# PoEpi_proto.net
KiCad netlist of a schematic drawn in EAGLE
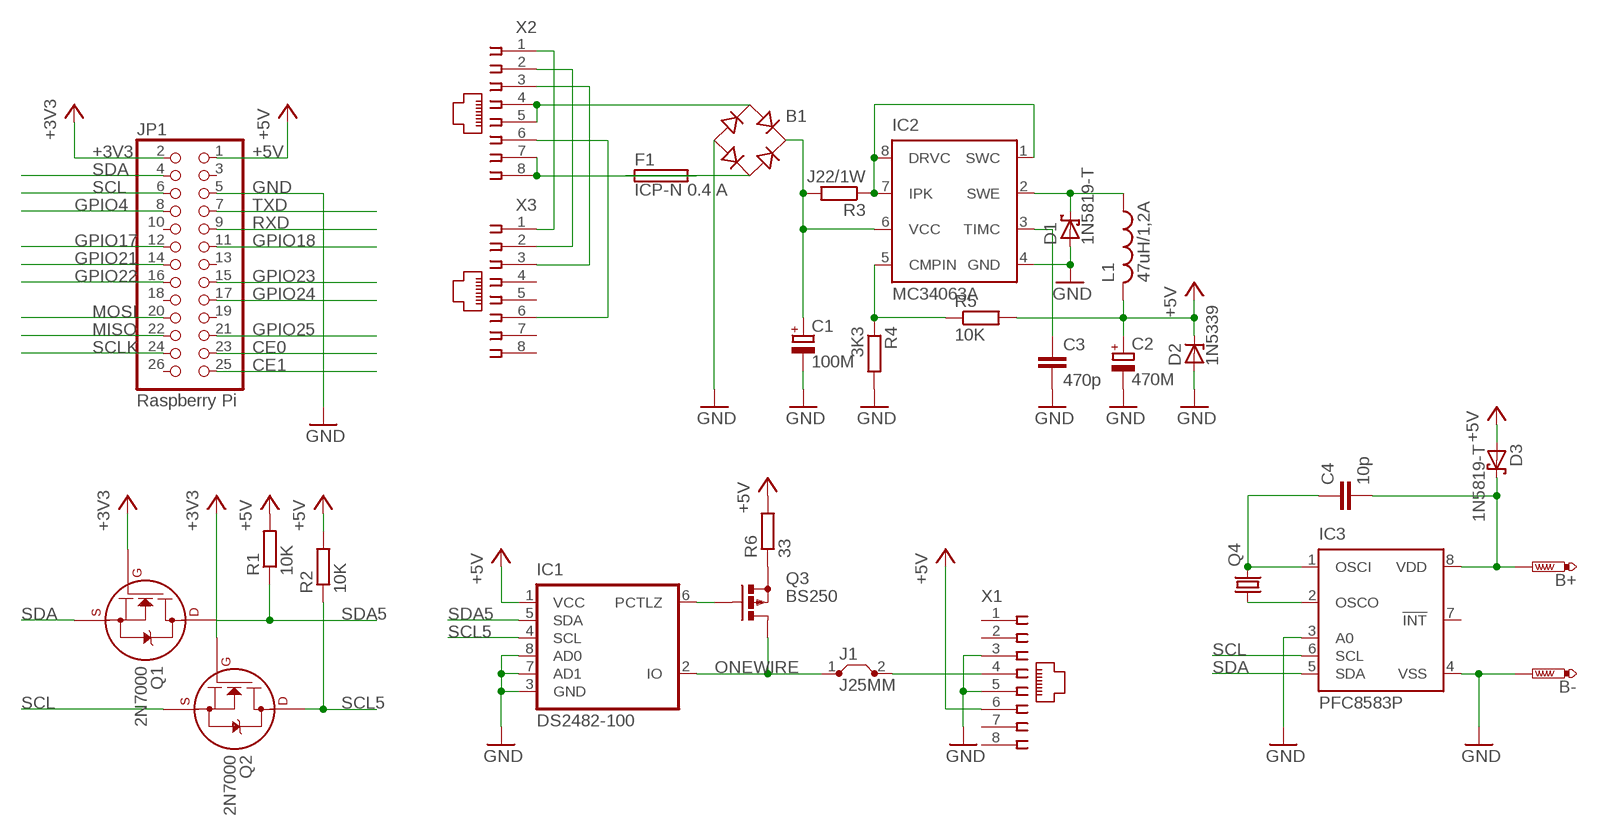
[diagram p0: schematic, sheet 1]

(export (version "E")
  (design (tool "Eeschema 10.0.6"))
  (components
    (comp (ref "B+")
      (value "PTR1PAD1-13Y")
      (footprint "eagle-import:P1-13Y")
      (libsource (lib "eagle-import") (part "PTR1PAD1-13Y"))
    )
    (comp (ref "B-")
      (value "PTR1PAD1-13Y")
      (footprint "eagle-import:P1-13Y")
      (libsource (lib "eagle-import") (part "PTR1PAD1-13Y"))
    )
    (comp (ref "B1")
      (value "B-DIL")
      (footprint "eagle-import:B-DIL")
      (libsource (lib "eagle-import") (part "B-DIL"))
    )
    (comp (ref "C1")
      (value "100M")
      (footprint "eagle-import:E3,5-8")
      (libsource (lib "eagle-import") (part "CPOL-EUE3.5-8"))
    )
    (comp (ref "C2")
      (value "470M")
      (footprint "eagle-import:E3,5-8")
      (libsource (lib "eagle-import") (part "CPOL-EUE3.5-8"))
    )
    (comp (ref "C3")
      (value "470p")
      (footprint "eagle-import:C050-024X044")
      (libsource (lib "eagle-import") (part "C-EU050-024X044"))
    )
    (comp (ref "C4")
      (value "10p")
      (footprint "eagle-import:C050-024X044")
      (libsource (lib "eagle-import") (part "C-EU050-024X044"))
    )
    (comp (ref "D1")
      (value "1N5819-T")
      (footprint "eagle-import:DO41-7.6")
      (libsource (lib "eagle-import") (part "1N5819-T"))
    )
    (comp (ref "D2")
      (value "1N5339")
      (footprint "eagle-import:C1702-15")
      (libsource (lib "eagle-import") (part "1N5333"))
    )
    (comp (ref "D3")
      (value "1N5819-T")
      (footprint "eagle-import:DO41-7.6")
      (libsource (lib "eagle-import") (part "1N5819-T"))
    )
    (comp (ref "F1")
      (value "ICP-N 0.4 A")
      (footprint "eagle-import:TO92-2")
      (libsource (lib "eagle-import") (part "FUSETO92-2"))
    )
    (comp (ref "IC1")
      (value "DS2482-100")
      (footprint "eagle-import:SO08")
      (libsource (lib "eagle-import") (part "DS2482-100"))
    )
    (comp (ref "IC2")
      (value "MC34063A")
      (footprint "eagle-import:DIL8")
      (libsource (lib "eagle-import") (part "MC34063A"))
    )
    (comp (ref "IC3")
      (value "PFC8583P")
      (footprint "eagle-import:DIL08")
      (libsource (lib "eagle-import") (part "PFC8583P"))
    )
    (comp (ref "J1")
      (value "J25MM")
      (footprint "eagle-import:25")
      (libsource (lib "eagle-import") (part "J25MM"))
    )
    (comp (ref "JP1")
      (value "Raspberry Pi")
      (footprint "eagle-import:2X13")
      (libsource (lib "eagle-import") (part "PINHD-2X13INV"))
    )
    (comp (ref "L1")
      (value "47uH/1,2A")
      (footprint "eagle-import:6000-XXXX-RC")
      (libsource (lib "eagle-import") (part "L-US6000-XXX-RC"))
    )
    (comp (ref "Q1")
      (value "2N7000")
      (footprint "eagle-import:TO-92")
      (libsource (lib "eagle-import") (part "2N700_TO920"))
    )
    (comp (ref "Q2")
      (value "2N7000")
      (footprint "eagle-import:TO-92")
      (libsource (lib "eagle-import") (part "2N700_TO920"))
    )
    (comp (ref "Q3")
      (value "BS250")
      (footprint "eagle-import:SOT54E")
      (libsource (lib "eagle-import") (part "BS250"))
    )
    (comp (ref "Q4")
      (value "CRYSTALTC26V")
      (footprint "eagle-import:TC26V")
      (libsource (lib "eagle-import") (part "CRYSTALTC26V"))
    )
    (comp (ref "R1")
      (value "10K")
      (footprint "eagle-import:0204_7")
      (libsource (lib "eagle-import") (part "R-EU_0204/7"))
    )
    (comp (ref "R2")
      (value "10K")
      (footprint "eagle-import:0204_7")
      (libsource (lib "eagle-import") (part "R-EU_0204/7"))
    )
    (comp (ref "R3")
      (value "J22/1W")
      (footprint "eagle-import:0617_17")
      (libsource (lib "eagle-import") (part "R-EU_0617/17"))
    )
    (comp (ref "R4")
      (value "3K3")
      (footprint "eagle-import:0204_7")
      (libsource (lib "eagle-import") (part "R-EU_0204/7"))
    )
    (comp (ref "R5")
      (value "10K")
      (footprint "eagle-import:0204_7")
      (libsource (lib "eagle-import") (part "R-EU_0204/7"))
    )
    (comp (ref "R6")
      (value "33")
      (footprint "eagle-import:0204_7")
      (libsource (lib "eagle-import") (part "R-EU_0204/7"))
    )
    (comp (ref "X1")
      (value "520251-4")
      (footprint "eagle-import:520251-4")
      (libsource (lib "eagle-import") (part "520251-4"))
    )
    (comp (ref "X2")
      (value "520251-4")
      (footprint "eagle-import:520251-4")
      (libsource (lib "eagle-import") (part "520251-4"))
    )
    (comp (ref "X3")
      (value "520251-4")
      (footprint "eagle-import:520251-4")
      (libsource (lib "eagle-import") (part "520251-4"))
    )
  )
  (nets
    (net (code "1") (name "+3V3") (class "Default")
      (node (ref "JP1") (pin "2") (pinfunction "1_2") (pintype "passive"))
      (node (ref "Q1") (pin "2") (pinfunction "G_2") (pintype "tri_state"))
      (node (ref "Q2") (pin "2") (pinfunction "G_2") (pintype "tri_state"))
    )
    (net (code "2") (name "+5V") (class "Default")
      (node (ref "C2") (pin "+") (pinfunction "+_+") (pintype "passive"))
      (node (ref "D2") (pin "C") (pinfunction "C_C") (pintype "passive"))
      (node (ref "D3") (pin "A") (pinfunction "A_A") (pintype "passive"))
      (node (ref "IC1") (pin "1") (pinfunction "VCC_1") (pintype "power_in"))
      (node (ref "JP1") (pin "1") (pinfunction "2_1") (pintype "passive"))
      (node (ref "L1") (pin "2") (pinfunction "2_2") (pintype "passive"))
      (node (ref "R1") (pin "2") (pinfunction "2_2") (pintype "passive"))
      (node (ref "R2") (pin "2") (pinfunction "2_2") (pintype "passive"))
      (node (ref "R5") (pin "2") (pinfunction "2_2") (pintype "passive"))
      (node (ref "R6") (pin "2") (pinfunction "2_2") (pintype "passive"))
      (node (ref "X1") (pin "6") (pinfunction "6_6") (pintype "passive"))
    )
    (net (code "3") (name "/CE0") (class "Default")
      (node (ref "JP1") (pin "23") (pinfunction "24_23") (pintype "passive"))
    )
    (net (code "4") (name "/CE1") (class "Default")
      (node (ref "JP1") (pin "25") (pinfunction "26_25") (pintype "passive"))
    )
    (net (code "5") (name "/GPIO4") (class "Default")
      (node (ref "JP1") (pin "8") (pinfunction "7_8") (pintype "passive"))
    )
    (net (code "6") (name "/GPIO17") (class "Default")
      (node (ref "JP1") (pin "12") (pinfunction "11_12") (pintype "passive"))
    )
    (net (code "7") (name "/GPIO18") (class "Default")
      (node (ref "JP1") (pin "11") (pinfunction "12_11") (pintype "passive"))
    )
    (net (code "8") (name "/GPIO21") (class "Default")
      (node (ref "JP1") (pin "14") (pinfunction "13_14") (pintype "passive"))
    )
    (net (code "9") (name "/GPIO22") (class "Default")
      (node (ref "JP1") (pin "16") (pinfunction "15_16") (pintype "passive"))
    )
    (net (code "10") (name "/GPIO23") (class "Default")
      (node (ref "JP1") (pin "15") (pinfunction "16_15") (pintype "passive"))
    )
    (net (code "11") (name "/GPIO24") (class "Default")
      (node (ref "JP1") (pin "17") (pinfunction "18_17") (pintype "passive"))
    )
    (net (code "12") (name "/GPIO25") (class "Default")
      (node (ref "JP1") (pin "21") (pinfunction "22_21") (pintype "passive"))
    )
    (net (code "13") (name "/MISO") (class "Default")
      (node (ref "JP1") (pin "22") (pinfunction "21_22") (pintype "passive"))
    )
    (net (code "14") (name "/MOSI") (class "Default")
      (node (ref "JP1") (pin "20") (pinfunction "19_20") (pintype "passive"))
    )
    (net (code "15") (name "/ONEWIRE") (class "Default")
      (node (ref "IC1") (pin "2") (pinfunction "IO_2") (pintype "bidirectional"))
      (node (ref "J1") (pin "1") (pinfunction "1_1") (pintype "passive"))
      (node (ref "Q3") (pin "D") (pinfunction "D_D") (pintype "passive"))
    )
    (net (code "16") (name "/RXD") (class "Default")
      (node (ref "JP1") (pin "9") (pinfunction "10_9") (pintype "passive"))
    )
    (net (code "17") (name "/SCL") (class "Default")
      (node (ref "IC3") (pin "6") (pinfunction "SCL_6") (pintype "input"))
      (node (ref "JP1") (pin "6") (pinfunction "5_6") (pintype "passive"))
      (node (ref "Q2") (pin "1") (pinfunction "S_1") (pintype "bidirectional"))
    )
    (net (code "18") (name "/SCL5") (class "Default")
      (node (ref "IC1") (pin "4") (pinfunction "SCL_4") (pintype "input"))
      (node (ref "Q2") (pin "3") (pinfunction "D_3") (pintype "bidirectional"))
      (node (ref "R2") (pin "1") (pinfunction "1_1") (pintype "passive"))
    )
    (net (code "19") (name "/SCLK") (class "Default")
      (node (ref "JP1") (pin "24") (pinfunction "23_24") (pintype "passive"))
    )
    (net (code "20") (name "/SDA") (class "Default")
      (node (ref "IC3") (pin "5") (pinfunction "SDA_5") (pintype "bidirectional"))
      (node (ref "JP1") (pin "4") (pinfunction "3_4") (pintype "passive"))
      (node (ref "Q1") (pin "1") (pinfunction "S_1") (pintype "bidirectional"))
    )
    (net (code "21") (name "/SDA5") (class "Default")
      (node (ref "IC1") (pin "5") (pinfunction "SDA_5") (pintype "input"))
      (node (ref "Q1") (pin "3") (pinfunction "D_3") (pintype "bidirectional"))
      (node (ref "R1") (pin "1") (pinfunction "1_1") (pintype "passive"))
    )
    (net (code "22") (name "/TXD") (class "Default")
      (node (ref "JP1") (pin "7") (pinfunction "8_7") (pintype "passive"))
    )
    (net (code "23") (name "GND") (class "Default")
      (node (ref "B-") (pin "TP") (pinfunction "TP_TP") (pintype "input"))
      (node (ref "B1") (pin "-") (pinfunction "-_-") (pintype "passive"))
      (node (ref "C1") (pin "-") (pinfunction "-_-") (pintype "passive"))
      (node (ref "C2") (pin "-") (pinfunction "-_-") (pintype "passive"))
      (node (ref "C3") (pin "2") (pinfunction "2_2") (pintype "passive"))
      (node (ref "D1") (pin "A") (pinfunction "A_A") (pintype "passive"))
      (node (ref "D2") (pin "A") (pinfunction "A_A") (pintype "passive"))
      (node (ref "IC1") (pin "3") (pinfunction "GND_3") (pintype "power_in"))
      (node (ref "IC1") (pin "7") (pinfunction "AD1_7") (pintype "bidirectional"))
      (node (ref "IC1") (pin "8") (pinfunction "AD0_8") (pintype "bidirectional"))
      (node (ref "IC2") (pin "4") (pinfunction "GND_4") (pintype "power_in"))
      (node (ref "IC3") (pin "3") (pinfunction "A0_3") (pintype "input"))
      (node (ref "IC3") (pin "4") (pinfunction "VSS_4") (pintype "power_in"))
      (node (ref "JP1") (pin "5") (pinfunction "6_5") (pintype "passive"))
      (node (ref "R4") (pin "2") (pinfunction "2_2") (pintype "passive"))
      (node (ref "X1") (pin "3") (pinfunction "3_3") (pintype "passive"))
      (node (ref "X1") (pin "5") (pinfunction "5_5") (pintype "passive"))
    )
    (net (code "24") (name "Net-(B1-PadAC1)") (class "Default")
      (node (ref "B1") (pin "AC1") (pinfunction "AC1_AC1") (pintype "passive"))
      (node (ref "X2") (pin "4") (pinfunction "4_4") (pintype "passive"))
      (node (ref "X2") (pin "5") (pinfunction "5_5") (pintype "passive"))
    )
    (net (code "25") (name "Net-(B1-PadAC2)") (class "Default")
      (node (ref "B1") (pin "AC2") (pinfunction "AC2_AC2") (pintype "passive"))
      (node (ref "F1") (pin "1") (pinfunction "1_1") (pintype "passive"))
    )
    (net (code "26") (name "Net-(F1-2)") (class "Default")
      (node (ref "F1") (pin "3") (pinfunction "2_3") (pintype "passive"))
      (node (ref "X2") (pin "7") (pinfunction "7_7") (pintype "passive"))
      (node (ref "X2") (pin "8") (pinfunction "8_8") (pintype "passive"))
    )
    (net (code "27") (name "Net-(IC1-PCTLZ)") (class "Default")
      (node (ref "IC1") (pin "6") (pinfunction "PCTLZ_6") (pintype "output"))
      (node (ref "Q3") (pin "G") (pinfunction "G_G") (pintype "passive"))
    )
    (net (code "28") (name "Net-(IC2-CMPIN)") (class "Default")
      (node (ref "IC2") (pin "5") (pinfunction "CMPIN_5") (pintype "input"))
      (node (ref "R4") (pin "1") (pinfunction "1_1") (pintype "passive"))
      (node (ref "R5") (pin "1") (pinfunction "1_1") (pintype "passive"))
    )
    (net (code "29") (name "Net-(IC2-DRVC)") (class "Default")
      (node (ref "IC2") (pin "1") (pinfunction "SWC_1") (pintype "open_collector"))
      (node (ref "IC2") (pin "7") (pinfunction "IPK_7") (pintype "input"))
      (node (ref "IC2") (pin "8") (pinfunction "DRVC_8") (pintype "input"))
      (node (ref "R3") (pin "1") (pinfunction "1_1") (pintype "passive"))
    )
    (net (code "30") (name "Net-(IC2-SWE)") (class "Default")
      (node (ref "D1") (pin "C") (pinfunction "C_C") (pintype "passive"))
      (node (ref "IC2") (pin "2") (pinfunction "SWE_2") (pintype "output"))
      (node (ref "L1") (pin "1") (pinfunction "1_1") (pintype "passive"))
    )
    (net (code "31") (name "Net-(IC2-TIMC)") (class "Default")
      (node (ref "C3") (pin "1") (pinfunction "1_1") (pintype "passive"))
      (node (ref "IC2") (pin "3") (pinfunction "TIMC_3") (pintype "output"))
    )
    (net (code "32") (name "Net-(IC2-VCC)") (class "Default")
      (node (ref "B1") (pin "+") (pinfunction "+_+") (pintype "passive"))
      (node (ref "C1") (pin "+") (pinfunction "+_+") (pintype "passive"))
      (node (ref "IC2") (pin "6") (pinfunction "VCC_6") (pintype "power_in"))
      (node (ref "R3") (pin "2") (pinfunction "2_2") (pintype "passive"))
    )
    (net (code "33") (name "Net-(IC3-OSCI)") (class "Default")
      (node (ref "C4") (pin "1") (pinfunction "1_1") (pintype "passive"))
      (node (ref "IC3") (pin "1") (pinfunction "OSCI_1") (pintype "input"))
      (node (ref "Q4") (pin "2") (pinfunction "2_2") (pintype "passive"))
    )
    (net (code "34") (name "Net-(IC3-OSCO)") (class "Default")
      (node (ref "IC3") (pin "2") (pinfunction "OSCO_2") (pintype "output"))
      (node (ref "Q4") (pin "1") (pinfunction "1_1") (pintype "passive"))
    )
    (net (code "35") (name "Net-(IC3-VDD)") (class "Default")
      (node (ref "B+") (pin "TP") (pinfunction "TP_TP") (pintype "input"))
      (node (ref "C4") (pin "2") (pinfunction "2_2") (pintype "passive"))
      (node (ref "D3") (pin "C") (pinfunction "C_C") (pintype "passive"))
      (node (ref "IC3") (pin "8") (pinfunction "VDD_8") (pintype "power_in"))
    )
    (net (code "36") (name "Net-(J1-Pad2)") (class "Default")
      (node (ref "J1") (pin "2") (pinfunction "2_2") (pintype "passive"))
      (node (ref "X1") (pin "4") (pinfunction "4_4") (pintype "passive"))
    )
    (net (code "37") (name "Net-(Q3-PadS)") (class "Default")
      (node (ref "Q3") (pin "S") (pinfunction "S_S") (pintype "passive"))
      (node (ref "R6") (pin "1") (pinfunction "1_1") (pintype "passive"))
    )
    (net (code "38") (name "Net-(X2-Pad1)") (class "Default")
      (node (ref "X2") (pin "1") (pinfunction "1_1") (pintype "passive"))
      (node (ref "X3") (pin "1") (pinfunction "1_1") (pintype "passive"))
    )
    (net (code "39") (name "Net-(X2-Pad2)") (class "Default")
      (node (ref "X2") (pin "2") (pinfunction "2_2") (pintype "passive"))
      (node (ref "X3") (pin "2") (pinfunction "2_2") (pintype "passive"))
    )
    (net (code "40") (name "Net-(X2-Pad3)") (class "Default")
      (node (ref "X2") (pin "3") (pinfunction "3_3") (pintype "passive"))
      (node (ref "X3") (pin "3") (pinfunction "3_3") (pintype "passive"))
    )
    (net (code "41") (name "Net-(X2-Pad6)") (class "Default")
      (node (ref "X2") (pin "6") (pinfunction "6_6") (pintype "passive"))
      (node (ref "X3") (pin "6") (pinfunction "6_6") (pintype "passive"))
    )
    (net (code "42") (name "unconnected-(IC3-~{INT}-Pad7)") (class "Default")
      (node (ref "IC3") (pin "7") (pinfunction "~{INT}_7") (pintype "output"))
    )
    (net (code "43") (name "unconnected-(JP1-4-Pad3)") (class "Default")
      (node (ref "JP1") (pin "3") (pinfunction "4_3") (pintype "passive"))
    )
    (net (code "44") (name "unconnected-(JP1-9-Pad10)") (class "Default")
      (node (ref "JP1") (pin "10") (pinfunction "9_10") (pintype "passive"))
    )
    (net (code "45") (name "unconnected-(JP1-14-Pad13)") (class "Default")
      (node (ref "JP1") (pin "13") (pinfunction "14_13") (pintype "passive"))
    )
    (net (code "46") (name "unconnected-(JP1-17-Pad18)") (class "Default")
      (node (ref "JP1") (pin "18") (pinfunction "17_18") (pintype "passive"))
    )
    (net (code "47") (name "unconnected-(JP1-20-Pad19)") (class "Default")
      (node (ref "JP1") (pin "19") (pinfunction "20_19") (pintype "passive"))
    )
    (net (code "48") (name "unconnected-(JP1-25-Pad26)") (class "Default")
      (node (ref "JP1") (pin "26") (pinfunction "25_26") (pintype "passive"))
    )
    (net (code "49") (name "unconnected-(X1-Pad1)") (class "Default")
      (node (ref "X1") (pin "1") (pinfunction "1_1") (pintype "passive"))
    )
    (net (code "50") (name "unconnected-(X1-Pad2)") (class "Default")
      (node (ref "X1") (pin "2") (pinfunction "2_2") (pintype "passive"))
    )
    (net (code "51") (name "unconnected-(X1-Pad7)") (class "Default")
      (node (ref "X1") (pin "7") (pinfunction "7_7") (pintype "passive"))
    )
    (net (code "52") (name "unconnected-(X1-Pad8)") (class "Default")
      (node (ref "X1") (pin "8") (pinfunction "8_8") (pintype "passive"))
    )
    (net (code "53") (name "unconnected-(X3-Pad4)") (class "Default")
      (node (ref "X3") (pin "4") (pinfunction "4_4") (pintype "passive"))
    )
    (net (code "54") (name "unconnected-(X3-Pad5)") (class "Default")
      (node (ref "X3") (pin "5") (pinfunction "5_5") (pintype "passive"))
    )
    (net (code "55") (name "unconnected-(X3-Pad7)") (class "Default")
      (node (ref "X3") (pin "7") (pinfunction "7_7") (pintype "passive"))
    )
    (net (code "56") (name "unconnected-(X3-Pad8)") (class "Default")
      (node (ref "X3") (pin "8") (pinfunction "8_8") (pintype "passive"))
    )
  )
)
